# QSTL_25P_ZIF_ZIF.net
KiCad netlist of a schematic drawn in Altium Designer
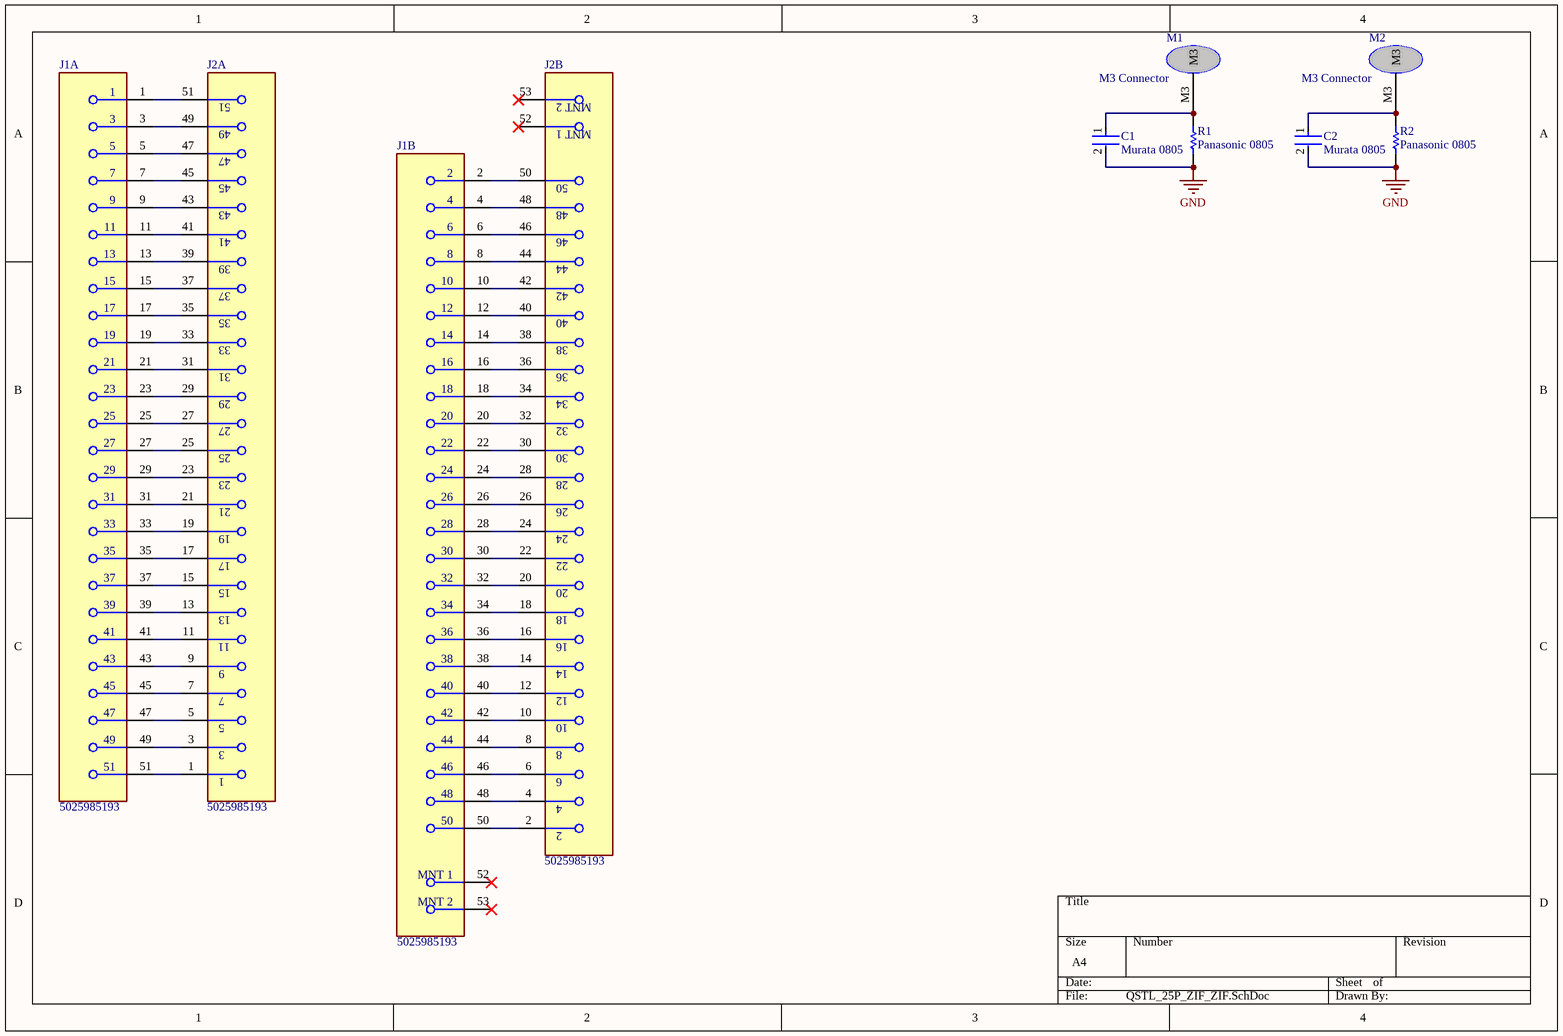
[diagram p0: QSTL_25P_ZIF_ZIF.SchDoc]

(export (version "E")
  (design (tool "Eeschema 10.0.6"))
  (components
    (comp (ref "C1")
      (value "Murata 0805")
      (footprint "FP-GRM21B-0_15-MFG")
      (description "Chip Multilayer Ceramic Capacitors for General Purpose, 0805, 10uF, X7R, 15%, 10%, 10V")
      (fields (field (name "TOLERANCE") "10%"))
      (libsource (lib "Altium Content Vault") (part "b4654b650e69147ec39a6b967a45e02"))
    )
    (comp (ref "C2")
      (value "Murata 0805")
      (footprint "FP-GRM21B-0_15-MFG")
      (description "Chip Multilayer Ceramic Capacitors for General Purpose, 0805, 10uF, X7R, 15%, 10%, 10V")
      (fields (field (name "TOLERANCE") "10%"))
      (libsource (lib "Altium Content Vault") (part "b4654b650e69147ec39a6b967a45e02"))
    )
    (comp (ref "J1")
      (value "5025985193")
      (footprint "FP-5025985193-MFG")
      (description "CONN FPC 51POS 0.30MM R/A")
      (fields
        (field (name "OCTOPART") "https://octopart.com/502598-5193-molex-33127991")
        (field (name "MANUFACTURER") "Molex")
      )
      (libsource (lib "Altium Content Vault") (part "2f3a718b51213836fa913b7fc1fd98d"))
    )
    (comp (ref "J2")
      (value "5025985193")
      (footprint "FP-5025985193-MFG")
      (description "CONN FPC 51POS 0.30MM R/A")
      (fields
        (field (name "OCTOPART") "https://octopart.com/502598-5193-molex-33127991")
        (field (name "MANUFACTURER") "Molex")
      )
      (libsource (lib "Altium Content Vault") (part "2f3a718b51213836fa913b7fc1fd98d"))
    )
    (comp (ref "M1") (value "M3 Connector") (footprint "M3") (libsource (lib "QSTL_25P_ZIF_ZIF") (part "M3")))
    (comp (ref "M2") (value "M3 Connector") (footprint "M3") (libsource (lib "QSTL_25P_ZIF_ZIF") (part "M3")))
    (comp (ref "R1")
      (value "Panasonic 0805")
      (footprint "RESC2013X60X40LL20T25")
      (fields (field (name "MANUFACTURER") "Panasonic") (field (name "PART NUMBER") "ERA6AEB222V"))
      (libsource (lib "Altium Content Vault") (part "RES"))
    )
    (comp (ref "R2")
      (value "Panasonic 0805")
      (footprint "RESC2013X60X40LL20T25")
      (fields (field (name "MANUFACTURER") "Panasonic") (field (name "PART NUMBER") "ERA6AEB222V"))
      (libsource (lib "Altium Content Vault") (part "RES"))
    )
  )
  (nets
    (net (code "1") (name "GND") (class "Default")
      (node (ref "C1") (pin "2") (pinfunction "2_2") (pintype "passive"))
      (node (ref "C2") (pin "2") (pinfunction "2_2") (pintype "passive"))
      (node (ref "R1") (pin "2") (pinfunction "2_2") (pintype "passive"))
      (node (ref "R2") (pin "2") (pinfunction "2_2") (pintype "passive"))
    )
    (net (code "2") (name "Net-(C1-Pad1)") (class "Default")
      (node (ref "C1") (pin "1") (pinfunction "1_1") (pintype "passive"))
      (node (ref "M1") (pin "M3") (pinfunction "M3_M3") (pintype "passive"))
      (node (ref "R1") (pin "1") (pinfunction "1_1") (pintype "passive"))
    )
    (net (code "3") (name "Net-(C2-Pad1)") (class "Default")
      (node (ref "C2") (pin "1") (pinfunction "1_1") (pintype "passive"))
      (node (ref "M2") (pin "M3") (pinfunction "M3_M3") (pintype "passive"))
      (node (ref "R2") (pin "1") (pinfunction "1_1") (pintype "passive"))
    )
    (net (code "4") (name "Net-(J1-Pad1)") (class "Default")
      (node (ref "J1") (pin "1") (pinfunction "1_1") (pintype "passive"))
      (node (ref "J2") (pin "51") (pinfunction "51_51") (pintype "passive"))
    )
    (net (code "5") (name "Net-(J1-Pad2)") (class "Default")
      (node (ref "J1") (pin "2") (pinfunction "2_2") (pintype "passive"))
      (node (ref "J2") (pin "50") (pinfunction "50_50") (pintype "passive"))
    )
    (net (code "6") (name "Net-(J1-Pad3)") (class "Default")
      (node (ref "J1") (pin "3") (pinfunction "3_3") (pintype "passive"))
      (node (ref "J2") (pin "49") (pinfunction "49_49") (pintype "passive"))
    )
    (net (code "7") (name "Net-(J1-Pad4)") (class "Default")
      (node (ref "J1") (pin "4") (pinfunction "4_4") (pintype "passive"))
      (node (ref "J2") (pin "48") (pinfunction "48_48") (pintype "passive"))
    )
    (net (code "8") (name "Net-(J1-Pad5)") (class "Default")
      (node (ref "J1") (pin "5") (pinfunction "5_5") (pintype "passive"))
      (node (ref "J2") (pin "47") (pinfunction "47_47") (pintype "passive"))
    )
    (net (code "9") (name "Net-(J1-Pad6)") (class "Default")
      (node (ref "J1") (pin "6") (pinfunction "6_6") (pintype "passive"))
      (node (ref "J2") (pin "46") (pinfunction "46_46") (pintype "passive"))
    )
    (net (code "10") (name "Net-(J1-Pad7)") (class "Default")
      (node (ref "J1") (pin "7") (pinfunction "7_7") (pintype "passive"))
      (node (ref "J2") (pin "45") (pinfunction "45_45") (pintype "passive"))
    )
    (net (code "11") (name "Net-(J1-Pad8)") (class "Default")
      (node (ref "J1") (pin "8") (pinfunction "8_8") (pintype "passive"))
      (node (ref "J2") (pin "44") (pinfunction "44_44") (pintype "passive"))
    )
    (net (code "12") (name "Net-(J1-Pad9)") (class "Default")
      (node (ref "J1") (pin "9") (pinfunction "9_9") (pintype "passive"))
      (node (ref "J2") (pin "43") (pinfunction "43_43") (pintype "passive"))
    )
    (net (code "13") (name "Net-(J1-Pad10)") (class "Default")
      (node (ref "J1") (pin "10") (pinfunction "10_10") (pintype "passive"))
      (node (ref "J2") (pin "42") (pinfunction "42_42") (pintype "passive"))
    )
    (net (code "14") (name "Net-(J1-Pad11)") (class "Default")
      (node (ref "J1") (pin "11") (pinfunction "11_11") (pintype "passive"))
      (node (ref "J2") (pin "41") (pinfunction "41_41") (pintype "passive"))
    )
    (net (code "15") (name "Net-(J1-Pad12)") (class "Default")
      (node (ref "J1") (pin "12") (pinfunction "12_12") (pintype "passive"))
      (node (ref "J2") (pin "40") (pinfunction "40_40") (pintype "passive"))
    )
    (net (code "16") (name "Net-(J1-Pad13)") (class "Default")
      (node (ref "J1") (pin "13") (pinfunction "13_13") (pintype "passive"))
      (node (ref "J2") (pin "39") (pinfunction "39_39") (pintype "passive"))
    )
    (net (code "17") (name "Net-(J1-Pad14)") (class "Default")
      (node (ref "J1") (pin "14") (pinfunction "14_14") (pintype "passive"))
      (node (ref "J2") (pin "38") (pinfunction "38_38") (pintype "passive"))
    )
    (net (code "18") (name "Net-(J1-Pad15)") (class "Default")
      (node (ref "J1") (pin "15") (pinfunction "15_15") (pintype "passive"))
      (node (ref "J2") (pin "37") (pinfunction "37_37") (pintype "passive"))
    )
    (net (code "19") (name "Net-(J1-Pad16)") (class "Default")
      (node (ref "J1") (pin "16") (pinfunction "16_16") (pintype "passive"))
      (node (ref "J2") (pin "36") (pinfunction "36_36") (pintype "passive"))
    )
    (net (code "20") (name "Net-(J1-Pad17)") (class "Default")
      (node (ref "J1") (pin "17") (pinfunction "17_17") (pintype "passive"))
      (node (ref "J2") (pin "35") (pinfunction "35_35") (pintype "passive"))
    )
    (net (code "21") (name "Net-(J1-Pad18)") (class "Default")
      (node (ref "J1") (pin "18") (pinfunction "18_18") (pintype "passive"))
      (node (ref "J2") (pin "34") (pinfunction "34_34") (pintype "passive"))
    )
    (net (code "22") (name "Net-(J1-Pad19)") (class "Default")
      (node (ref "J1") (pin "19") (pinfunction "19_19") (pintype "passive"))
      (node (ref "J2") (pin "33") (pinfunction "33_33") (pintype "passive"))
    )
    (net (code "23") (name "Net-(J1-Pad20)") (class "Default")
      (node (ref "J1") (pin "20") (pinfunction "20_20") (pintype "passive"))
      (node (ref "J2") (pin "32") (pinfunction "32_32") (pintype "passive"))
    )
    (net (code "24") (name "Net-(J1-Pad21)") (class "Default")
      (node (ref "J1") (pin "21") (pinfunction "21_21") (pintype "passive"))
      (node (ref "J2") (pin "31") (pinfunction "31_31") (pintype "passive"))
    )
    (net (code "25") (name "Net-(J1-Pad22)") (class "Default")
      (node (ref "J1") (pin "22") (pinfunction "22_22") (pintype "passive"))
      (node (ref "J2") (pin "30") (pinfunction "30_30") (pintype "passive"))
    )
    (net (code "26") (name "Net-(J1-Pad23)") (class "Default")
      (node (ref "J1") (pin "23") (pinfunction "23_23") (pintype "passive"))
      (node (ref "J2") (pin "29") (pinfunction "29_29") (pintype "passive"))
    )
    (net (code "27") (name "Net-(J1-Pad24)") (class "Default")
      (node (ref "J1") (pin "24") (pinfunction "24_24") (pintype "passive"))
      (node (ref "J2") (pin "28") (pinfunction "28_28") (pintype "passive"))
    )
    (net (code "28") (name "Net-(J1-Pad25)") (class "Default")
      (node (ref "J1") (pin "25") (pinfunction "25_25") (pintype "passive"))
      (node (ref "J2") (pin "27") (pinfunction "27_27") (pintype "passive"))
    )
    (net (code "29") (name "Net-(J1-Pad26)") (class "Default")
      (node (ref "J1") (pin "26") (pinfunction "26_26") (pintype "passive"))
      (node (ref "J2") (pin "26") (pinfunction "26_26") (pintype "passive"))
    )
    (net (code "30") (name "Net-(J1-Pad27)") (class "Default")
      (node (ref "J1") (pin "27") (pinfunction "27_27") (pintype "passive"))
      (node (ref "J2") (pin "25") (pinfunction "25_25") (pintype "passive"))
    )
    (net (code "31") (name "Net-(J1-Pad28)") (class "Default")
      (node (ref "J1") (pin "28") (pinfunction "28_28") (pintype "passive"))
      (node (ref "J2") (pin "24") (pinfunction "24_24") (pintype "passive"))
    )
    (net (code "32") (name "Net-(J1-Pad29)") (class "Default")
      (node (ref "J1") (pin "29") (pinfunction "29_29") (pintype "passive"))
      (node (ref "J2") (pin "23") (pinfunction "23_23") (pintype "passive"))
    )
    (net (code "33") (name "Net-(J1-Pad30)") (class "Default")
      (node (ref "J1") (pin "30") (pinfunction "30_30") (pintype "passive"))
      (node (ref "J2") (pin "22") (pinfunction "22_22") (pintype "passive"))
    )
    (net (code "34") (name "Net-(J1-Pad31)") (class "Default")
      (node (ref "J1") (pin "31") (pinfunction "31_31") (pintype "passive"))
      (node (ref "J2") (pin "21") (pinfunction "21_21") (pintype "passive"))
    )
    (net (code "35") (name "Net-(J1-Pad32)") (class "Default")
      (node (ref "J1") (pin "32") (pinfunction "32_32") (pintype "passive"))
      (node (ref "J2") (pin "20") (pinfunction "20_20") (pintype "passive"))
    )
    (net (code "36") (name "Net-(J1-Pad33)") (class "Default")
      (node (ref "J1") (pin "33") (pinfunction "33_33") (pintype "passive"))
      (node (ref "J2") (pin "19") (pinfunction "19_19") (pintype "passive"))
    )
    (net (code "37") (name "Net-(J1-Pad34)") (class "Default")
      (node (ref "J1") (pin "34") (pinfunction "34_34") (pintype "passive"))
      (node (ref "J2") (pin "18") (pinfunction "18_18") (pintype "passive"))
    )
    (net (code "38") (name "Net-(J1-Pad35)") (class "Default")
      (node (ref "J1") (pin "35") (pinfunction "35_35") (pintype "passive"))
      (node (ref "J2") (pin "17") (pinfunction "17_17") (pintype "passive"))
    )
    (net (code "39") (name "Net-(J1-Pad36)") (class "Default")
      (node (ref "J1") (pin "36") (pinfunction "36_36") (pintype "passive"))
      (node (ref "J2") (pin "16") (pinfunction "16_16") (pintype "passive"))
    )
    (net (code "40") (name "Net-(J1-Pad37)") (class "Default")
      (node (ref "J1") (pin "37") (pinfunction "37_37") (pintype "passive"))
      (node (ref "J2") (pin "15") (pinfunction "15_15") (pintype "passive"))
    )
    (net (code "41") (name "Net-(J1-Pad38)") (class "Default")
      (node (ref "J1") (pin "38") (pinfunction "38_38") (pintype "passive"))
      (node (ref "J2") (pin "14") (pinfunction "14_14") (pintype "passive"))
    )
    (net (code "42") (name "Net-(J1-Pad39)") (class "Default")
      (node (ref "J1") (pin "39") (pinfunction "39_39") (pintype "passive"))
      (node (ref "J2") (pin "13") (pinfunction "13_13") (pintype "passive"))
    )
    (net (code "43") (name "Net-(J1-Pad40)") (class "Default")
      (node (ref "J1") (pin "40") (pinfunction "40_40") (pintype "passive"))
      (node (ref "J2") (pin "12") (pinfunction "12_12") (pintype "passive"))
    )
    (net (code "44") (name "Net-(J1-Pad41)") (class "Default")
      (node (ref "J1") (pin "41") (pinfunction "41_41") (pintype "passive"))
      (node (ref "J2") (pin "11") (pinfunction "11_11") (pintype "passive"))
    )
    (net (code "45") (name "Net-(J1-Pad42)") (class "Default")
      (node (ref "J1") (pin "42") (pinfunction "42_42") (pintype "passive"))
      (node (ref "J2") (pin "10") (pinfunction "10_10") (pintype "passive"))
    )
    (net (code "46") (name "Net-(J1-Pad43)") (class "Default")
      (node (ref "J1") (pin "43") (pinfunction "43_43") (pintype "passive"))
      (node (ref "J2") (pin "9") (pinfunction "9_9") (pintype "passive"))
    )
    (net (code "47") (name "Net-(J1-Pad44)") (class "Default")
      (node (ref "J1") (pin "44") (pinfunction "44_44") (pintype "passive"))
      (node (ref "J2") (pin "8") (pinfunction "8_8") (pintype "passive"))
    )
    (net (code "48") (name "Net-(J1-Pad45)") (class "Default")
      (node (ref "J1") (pin "45") (pinfunction "45_45") (pintype "passive"))
      (node (ref "J2") (pin "7") (pinfunction "7_7") (pintype "passive"))
    )
    (net (code "49") (name "Net-(J1-Pad46)") (class "Default")
      (node (ref "J1") (pin "46") (pinfunction "46_46") (pintype "passive"))
      (node (ref "J2") (pin "6") (pinfunction "6_6") (pintype "passive"))
    )
    (net (code "50") (name "Net-(J1-Pad47)") (class "Default")
      (node (ref "J1") (pin "47") (pinfunction "47_47") (pintype "passive"))
      (node (ref "J2") (pin "5") (pinfunction "5_5") (pintype "passive"))
    )
    (net (code "51") (name "Net-(J1-Pad48)") (class "Default")
      (node (ref "J1") (pin "48") (pinfunction "48_48") (pintype "passive"))
      (node (ref "J2") (pin "4") (pinfunction "4_4") (pintype "passive"))
    )
    (net (code "52") (name "Net-(J1-Pad49)") (class "Default")
      (node (ref "J1") (pin "49") (pinfunction "49_49") (pintype "passive"))
      (node (ref "J2") (pin "3") (pinfunction "3_3") (pintype "passive"))
    )
    (net (code "53") (name "Net-(J1-Pad50)") (class "Default")
      (node (ref "J1") (pin "50") (pinfunction "50_50") (pintype "passive"))
      (node (ref "J2") (pin "2") (pinfunction "2_2") (pintype "passive"))
    )
    (net (code "54") (name "Net-(J1-Pad51)") (class "Default")
      (node (ref "J1") (pin "51") (pinfunction "51_51") (pintype "passive"))
      (node (ref "J2") (pin "1") (pinfunction "1_1") (pintype "passive"))
    )
    (net (code "55") (name "unconnected-(J1B-MNT_1-Pad52)") (class "Default")
      (node (ref "J1") (pin "52") (pinfunction "MNT_1_52") (pintype "passive+no_connect"))
    )
    (net (code "56") (name "unconnected-(J1B-MNT_2-Pad53)") (class "Default")
      (node (ref "J1") (pin "53") (pinfunction "MNT_2_53") (pintype "passive+no_connect"))
    )
    (net (code "57") (name "unconnected-(J2B-MNT_1-Pad52)") (class "Default")
      (node (ref "J2") (pin "52") (pinfunction "MNT_1_52") (pintype "passive+no_connect"))
    )
    (net (code "58") (name "unconnected-(J2B-MNT_2-Pad53)") (class "Default")
      (node (ref "J2") (pin "53") (pinfunction "MNT_2_53") (pintype "passive+no_connect"))
    )
  )
)
